# LogicBlocks-splitter.net
KiCad netlist of a schematic drawn in EAGLE
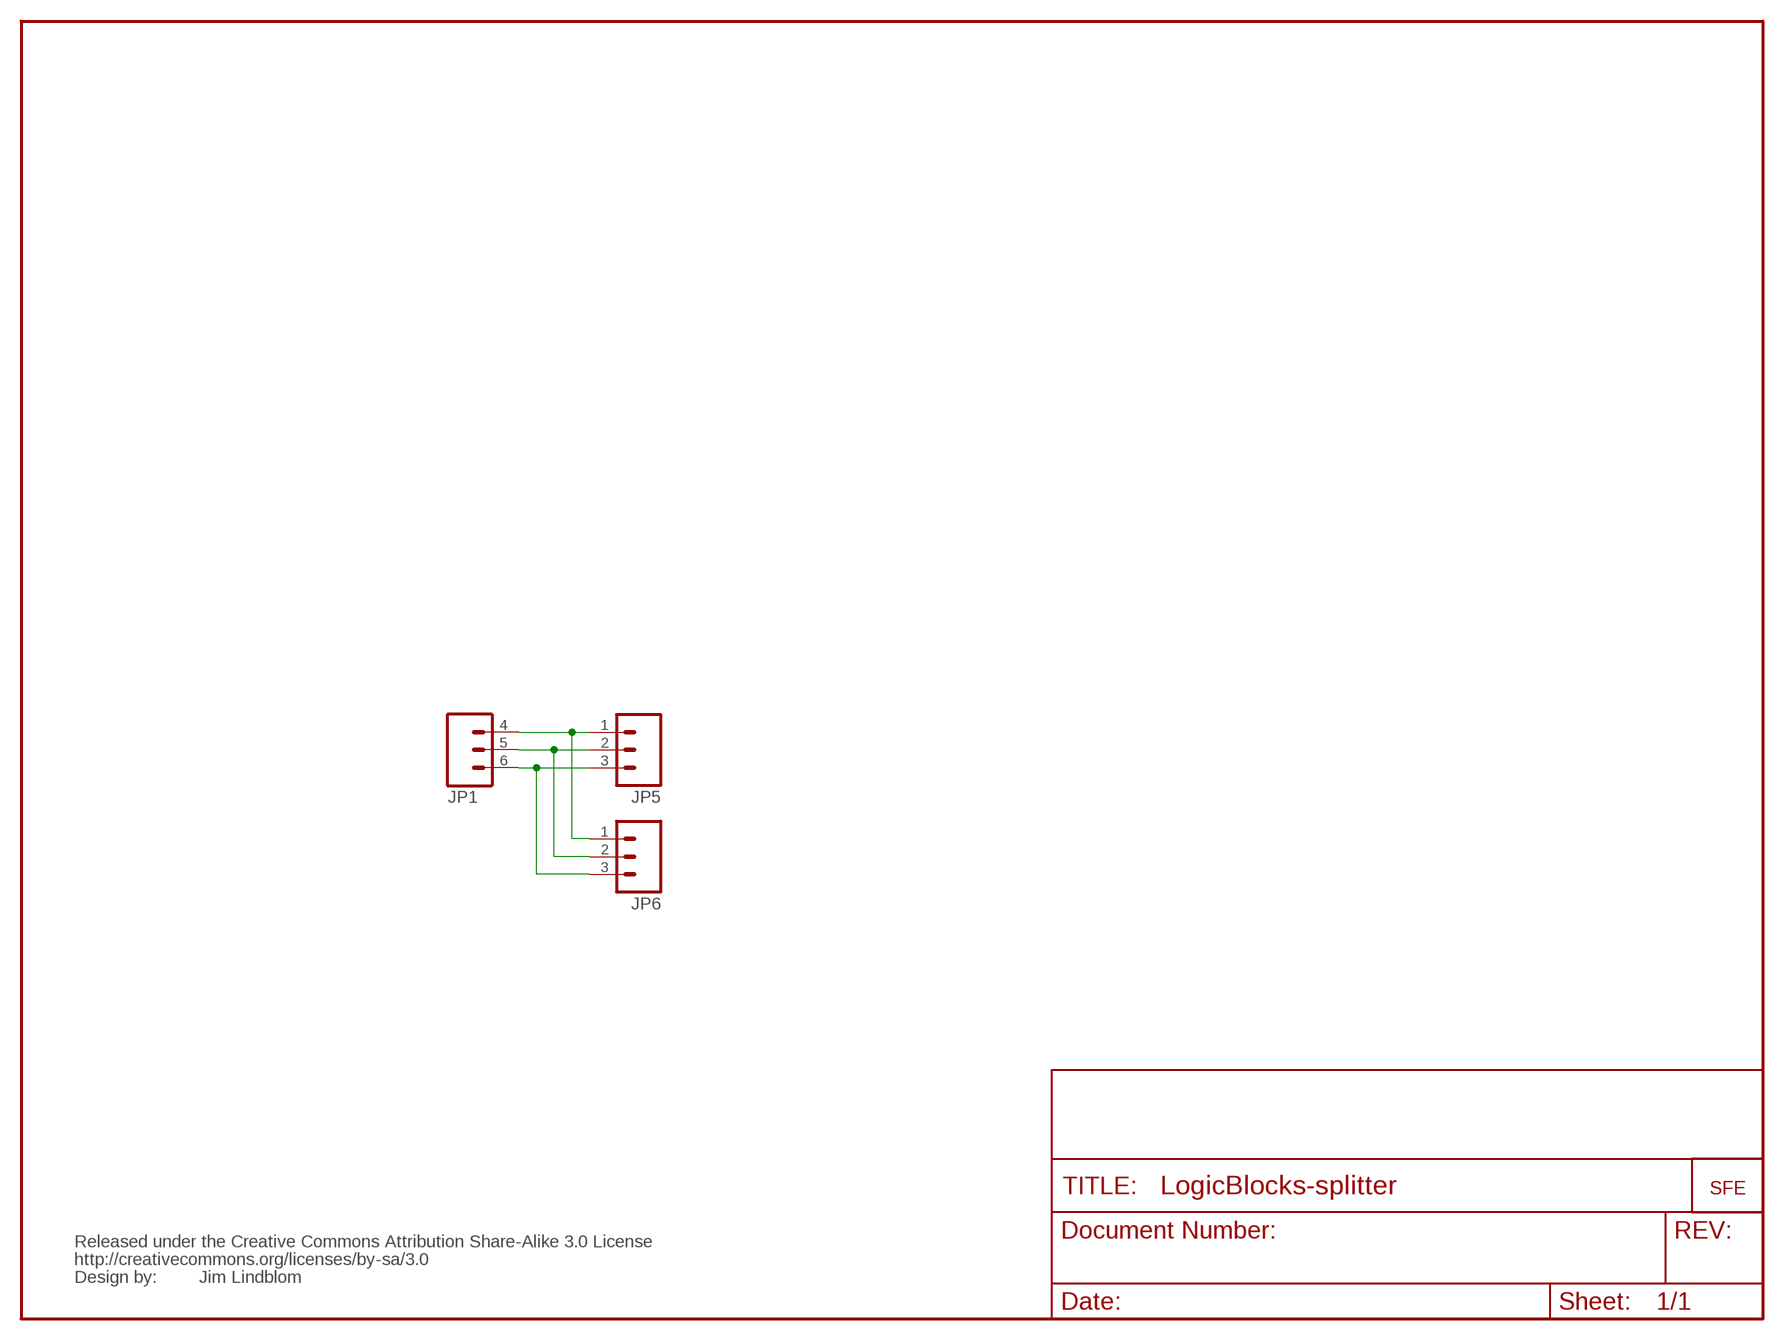
[diagram p0: schematic, sheet 1]

(export (version "E")
  (design (tool "Eeschema 10.0.6"))
  (components
    (comp (ref "JP1")
      (value "M03SMD-RA-FEMALE")
      (footprint "eagle-import:1X03-SMD-FEMALE")
      (libsource (lib "eagle-import") (part "M03SMD-RA-FEMALE"))
    )
    (comp (ref "JP4")
      (value "LOGO-SFESK")
      (footprint "eagle-import:SFE-LOGO-FLAME")
      (libsource (lib "eagle-import") (part "LOGO-SFESK"))
    )
    (comp (ref "JP5")
      (value "M03SMD_RA_MALE_POST")
      (footprint "eagle-import:1X03_SMD_RA_MALE_POST")
      (libsource (lib "eagle-import") (part "M03SMD_RA_MALE_POST"))
    )
    (comp (ref "JP6")
      (value "M03SMD_RA_MALE_POST")
      (footprint "eagle-import:1X03_SMD_RA_MALE_POST")
      (libsource (lib "eagle-import") (part "M03SMD_RA_MALE_POST"))
    )
    (comp (ref "U$1")
      (value "CREATIVE_COMMONS")
      (footprint "eagle-import:CREATIVE_COMMONS")
      (libsource (lib "eagle-import") (part "CREATIVE_COMMONS"))
    )
  )
  (nets
    (net (code "1") (name "Net-(JP1-1)") (class "Default")
      (node (ref "JP1") (pin "4") (pinfunction "1_4") (pintype "passive"))
      (node (ref "JP5") (pin "1") (pinfunction "1_1") (pintype "passive"))
      (node (ref "JP6") (pin "1") (pinfunction "1_1") (pintype "passive"))
    )
    (net (code "2") (name "Net-(JP1-2)") (class "Default")
      (node (ref "JP1") (pin "5") (pinfunction "2_5") (pintype "passive"))
      (node (ref "JP5") (pin "2") (pinfunction "2_2") (pintype "passive"))
      (node (ref "JP6") (pin "2") (pinfunction "2_2") (pintype "passive"))
    )
    (net (code "3") (name "Net-(JP1-3)") (class "Default")
      (node (ref "JP1") (pin "6") (pinfunction "3_6") (pintype "passive"))
      (node (ref "JP5") (pin "3") (pinfunction "3_3") (pintype "passive"))
      (node (ref "JP6") (pin "3") (pinfunction "3_3") (pintype "passive"))
    )
  )
)
